# 2_layers.net
KiCad netlist of a schematic drawn in EAGLE
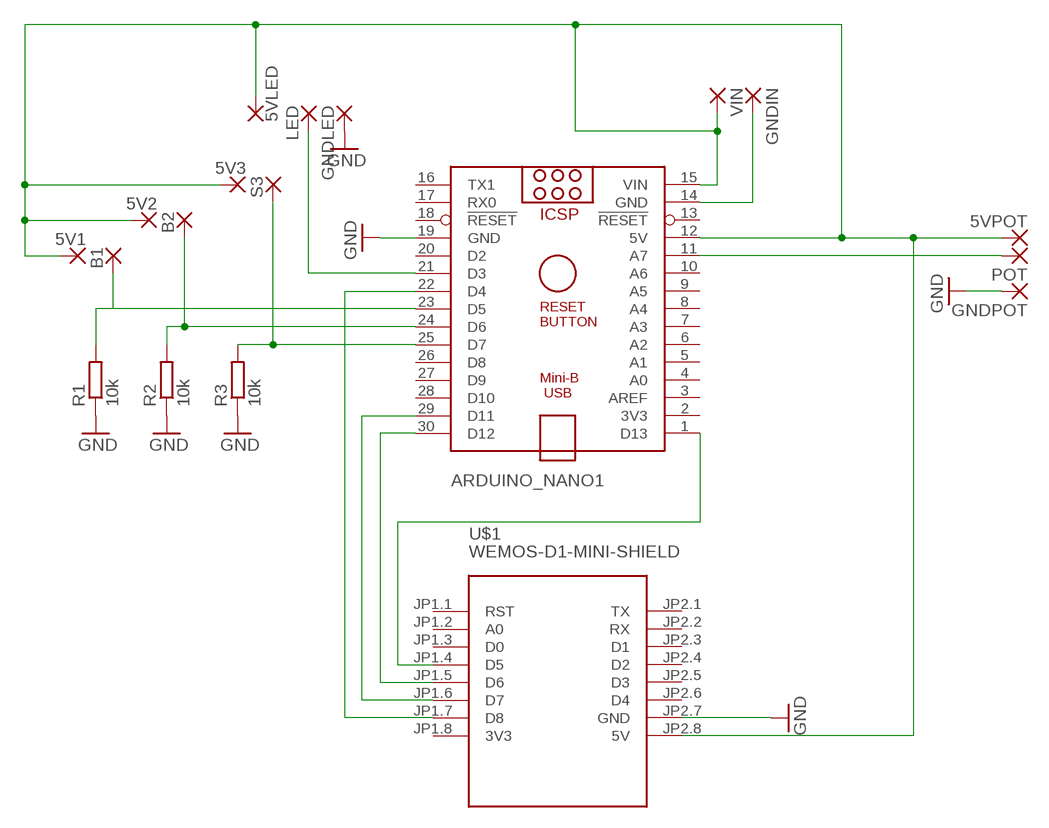
[diagram p0: schematic, sheet 1]

(export (version "E")
  (design (tool "Eeschema 10.0.6"))
  (components
    (comp (ref "5V1")
      (value "1,6/0,8")
      (footprint "eagle-import:1,6_0,8")
      (libsource (lib "eagle-import") (part "1,6/0,8"))
    )
    (comp (ref "5V2")
      (value "1,6/0,8")
      (footprint "eagle-import:1,6_0,8")
      (libsource (lib "eagle-import") (part "1,6/0,8"))
    )
    (comp (ref "5V3")
      (value "1,6/0,8")
      (footprint "eagle-import:1,6_0,8")
      (libsource (lib "eagle-import") (part "1,6/0,8"))
    )
    (comp (ref "5VLED")
      (value "1,6/0,8")
      (footprint "eagle-import:1,6_0,8")
      (libsource (lib "eagle-import") (part "1,6/0,8"))
    )
    (comp (ref "5VPOT")
      (value "1,6/0,8")
      (footprint "eagle-import:1,6_0,8")
      (libsource (lib "eagle-import") (part "1,6/0,8"))
    )
    (comp (ref "ARDUINO_NANO1")
      (value "ARDUINO_NANO")
      (footprint "eagle-import:ARDUINO_NANO")
      (libsource (lib "eagle-import") (part "ARDUINO_NANO"))
    )
    (comp (ref "B1")
      (value "1,6/0,8")
      (footprint "eagle-import:1,6_0,8")
      (libsource (lib "eagle-import") (part "1,6/0,8"))
    )
    (comp (ref "B2")
      (value "1,6/0,8")
      (footprint "eagle-import:1,6_0,8")
      (libsource (lib "eagle-import") (part "1,6/0,8"))
    )
    (comp (ref "GNDIN")
      (value "1,6/0,8")
      (footprint "eagle-import:1,6_0,8")
      (libsource (lib "eagle-import") (part "1,6/0,8"))
    )
    (comp (ref "GNDLED")
      (value "1,6/0,8")
      (footprint "eagle-import:1,6_0,8")
      (libsource (lib "eagle-import") (part "1,6/0,8"))
    )
    (comp (ref "GNDPOT")
      (value "1,6/0,8")
      (footprint "eagle-import:1,6_0,8")
      (libsource (lib "eagle-import") (part "1,6/0,8"))
    )
    (comp (ref "LED")
      (value "1,6/0,8")
      (footprint "eagle-import:1,6_0,8")
      (libsource (lib "eagle-import") (part "1,6/0,8"))
    )
    (comp (ref "POT")
      (value "1,6/0,8")
      (footprint "eagle-import:1,6_0,8")
      (libsource (lib "eagle-import") (part "1,6/0,8"))
    )
    (comp (ref "R1")
      (value "10k")
      (footprint "eagle-import:0207_7")
      (libsource (lib "eagle-import") (part "R-EU_0207/7"))
    )
    (comp (ref "R2")
      (value "10k")
      (footprint "eagle-import:0207_7")
      (libsource (lib "eagle-import") (part "R-EU_0207/7"))
    )
    (comp (ref "R3")
      (value "10k")
      (footprint "eagle-import:0207_7")
      (libsource (lib "eagle-import") (part "R-EU_0207/7"))
    )
    (comp (ref "S3")
      (value "1,6/0,8")
      (footprint "eagle-import:1,6_0,8")
      (libsource (lib "eagle-import") (part "1,6/0,8"))
    )
    (comp (ref "U$1")
      (value "WEMOS-D1-MINI-SHIELD")
      (footprint "eagle-import:WEMOS-D1-MINI-SHIELD")
      (libsource (lib "eagle-import") (part "WEMOS-D1-MINI-SHIELD"))
    )
    (comp (ref "VIN")
      (value "1,6/0,8")
      (footprint "eagle-import:1,6_0,8")
      (libsource (lib "eagle-import") (part "1,6/0,8"))
    )
  )
  (nets
    (net (code "1") (name "/3V3") (class "Default")
      (node (ref "U$1") (pin "JP1.8") (pinfunction "3V3_JP1.8") (pintype "power_in"))
    )
    (net (code "2") (name "GND") (class "Default")
      (node (ref "ARDUINO_NANO1") (pin "19") (pinfunction "GND_19") (pintype "power_in"))
      (node (ref "GNDLED") (pin "1") (pinfunction "P_1") (pintype "passive"))
      (node (ref "GNDPOT") (pin "1") (pinfunction "P_1") (pintype "passive"))
      (node (ref "R1") (pin "1") (pinfunction "1_1") (pintype "passive"))
      (node (ref "R2") (pin "1") (pinfunction "1_1") (pintype "passive"))
      (node (ref "R3") (pin "1") (pinfunction "1_1") (pintype "passive"))
      (node (ref "U$1") (pin "JP2.7") (pinfunction "GND_JP2.7") (pintype "power_in"))
    )
    (net (code "3") (name "Net-(5V1-P)") (class "Default")
      (node (ref "5V1") (pin "1") (pinfunction "P_1") (pintype "passive"))
      (node (ref "5V2") (pin "1") (pinfunction "P_1") (pintype "passive"))
      (node (ref "5V3") (pin "1") (pinfunction "P_1") (pintype "passive"))
      (node (ref "5VLED") (pin "1") (pinfunction "P_1") (pintype "passive"))
      (node (ref "5VPOT") (pin "1") (pinfunction "P_1") (pintype "passive"))
      (node (ref "ARDUINO_NANO1") (pin "12") (pinfunction "5V_12") (pintype "power_in"))
      (node (ref "ARDUINO_NANO1") (pin "15") (pinfunction "VIN_15") (pintype "power_in"))
      (node (ref "U$1") (pin "JP2.8") (pinfunction "5V_JP2.8") (pintype "power_in"))
      (node (ref "VIN") (pin "1") (pinfunction "P_1") (pintype "passive"))
    )
    (net (code "4") (name "Net-(ARDUINO_NANO1-A7)") (class "Default")
      (node (ref "ARDUINO_NANO1") (pin "11") (pinfunction "A7_11") (pintype "bidirectional"))
      (node (ref "POT") (pin "1") (pinfunction "P_1") (pintype "passive"))
    )
    (net (code "5") (name "Net-(ARDUINO_NANO1-D3)") (class "Default")
      (node (ref "ARDUINO_NANO1") (pin "21") (pinfunction "D3_21") (pintype "bidirectional"))
      (node (ref "LED") (pin "1") (pinfunction "P_1") (pintype "passive"))
    )
    (net (code "6") (name "Net-(ARDUINO_NANO1-D4)") (class "Default")
      (node (ref "ARDUINO_NANO1") (pin "22") (pinfunction "D4_22") (pintype "bidirectional"))
      (node (ref "U$1") (pin "JP1.7") (pinfunction "D8_JP1.7") (pintype "bidirectional"))
    )
    (net (code "7") (name "Net-(ARDUINO_NANO1-D5)") (class "Default")
      (node (ref "ARDUINO_NANO1") (pin "23") (pinfunction "D5_23") (pintype "bidirectional"))
      (node (ref "B1") (pin "1") (pinfunction "P_1") (pintype "passive"))
      (node (ref "R1") (pin "2") (pinfunction "2_2") (pintype "passive"))
    )
    (net (code "8") (name "Net-(ARDUINO_NANO1-D6)") (class "Default")
      (node (ref "ARDUINO_NANO1") (pin "24") (pinfunction "D6_24") (pintype "bidirectional"))
      (node (ref "B2") (pin "1") (pinfunction "P_1") (pintype "passive"))
      (node (ref "R2") (pin "2") (pinfunction "2_2") (pintype "passive"))
    )
    (net (code "9") (name "Net-(ARDUINO_NANO1-D7)") (class "Default")
      (node (ref "ARDUINO_NANO1") (pin "25") (pinfunction "D7_25") (pintype "bidirectional"))
      (node (ref "R3") (pin "2") (pinfunction "2_2") (pintype "passive"))
      (node (ref "S3") (pin "1") (pinfunction "P_1") (pintype "passive"))
    )
    (net (code "10") (name "Net-(ARDUINO_NANO1-D11)") (class "Default")
      (node (ref "ARDUINO_NANO1") (pin "29") (pinfunction "D11_29") (pintype "bidirectional"))
      (node (ref "U$1") (pin "JP1.6") (pinfunction "D7_JP1.6") (pintype "bidirectional"))
    )
    (net (code "11") (name "Net-(ARDUINO_NANO1-D12)") (class "Default")
      (node (ref "ARDUINO_NANO1") (pin "30") (pinfunction "D12_30") (pintype "bidirectional"))
      (node (ref "U$1") (pin "JP1.5") (pinfunction "D6_JP1.5") (pintype "bidirectional"))
    )
    (net (code "12") (name "Net-(ARDUINO_NANO1-D13)") (class "Default")
      (node (ref "ARDUINO_NANO1") (pin "1") (pinfunction "D13_1") (pintype "bidirectional"))
      (node (ref "U$1") (pin "JP1.4") (pinfunction "D5_JP1.4") (pintype "bidirectional"))
    )
    (net (code "13") (name "Net-(GNDIN-P)") (class "Default")
      (node (ref "ARDUINO_NANO1") (pin "14") (pinfunction "GND_14") (pintype "power_in"))
      (node (ref "GNDIN") (pin "1") (pinfunction "P_1") (pintype "passive"))
    )
    (net (code "14") (name "unconnected-(ARDUINO_NANO1-3V3-Pad2)") (class "Default")
      (node (ref "ARDUINO_NANO1") (pin "2") (pinfunction "3V3_2") (pintype "output"))
    )
    (net (code "15") (name "unconnected-(ARDUINO_NANO1-A0-Pad4)") (class "Default")
      (node (ref "ARDUINO_NANO1") (pin "4") (pinfunction "A0_4") (pintype "bidirectional"))
    )
    (net (code "16") (name "unconnected-(ARDUINO_NANO1-A1-Pad5)") (class "Default")
      (node (ref "ARDUINO_NANO1") (pin "5") (pinfunction "A1_5") (pintype "bidirectional"))
    )
    (net (code "17") (name "unconnected-(ARDUINO_NANO1-A2-Pad6)") (class "Default")
      (node (ref "ARDUINO_NANO1") (pin "6") (pinfunction "A2_6") (pintype "bidirectional"))
    )
    (net (code "18") (name "unconnected-(ARDUINO_NANO1-A3-Pad7)") (class "Default")
      (node (ref "ARDUINO_NANO1") (pin "7") (pinfunction "A3_7") (pintype "bidirectional"))
    )
    (net (code "19") (name "unconnected-(ARDUINO_NANO1-A4-Pad8)") (class "Default")
      (node (ref "ARDUINO_NANO1") (pin "8") (pinfunction "A4_8") (pintype "bidirectional"))
    )
    (net (code "20") (name "unconnected-(ARDUINO_NANO1-A5-Pad9)") (class "Default")
      (node (ref "ARDUINO_NANO1") (pin "9") (pinfunction "A5_9") (pintype "bidirectional"))
    )
    (net (code "21") (name "unconnected-(ARDUINO_NANO1-A6-Pad10)") (class "Default")
      (node (ref "ARDUINO_NANO1") (pin "10") (pinfunction "A6_10") (pintype "bidirectional"))
    )
    (net (code "22") (name "unconnected-(ARDUINO_NANO1-AREF-Pad3)") (class "Default")
      (node (ref "ARDUINO_NANO1") (pin "3") (pinfunction "AREF_3") (pintype "input"))
    )
    (net (code "23") (name "unconnected-(ARDUINO_NANO1-D2-Pad20)") (class "Default")
      (node (ref "ARDUINO_NANO1") (pin "20") (pinfunction "D2_20") (pintype "bidirectional"))
    )
    (net (code "24") (name "unconnected-(ARDUINO_NANO1-D8-Pad26)") (class "Default")
      (node (ref "ARDUINO_NANO1") (pin "26") (pinfunction "D8_26") (pintype "bidirectional"))
    )
    (net (code "25") (name "unconnected-(ARDUINO_NANO1-D9-Pad27)") (class "Default")
      (node (ref "ARDUINO_NANO1") (pin "27") (pinfunction "D9_27") (pintype "bidirectional"))
    )
    (net (code "26") (name "unconnected-(ARDUINO_NANO1-D10-Pad28)") (class "Default")
      (node (ref "ARDUINO_NANO1") (pin "28") (pinfunction "D10_28") (pintype "bidirectional"))
    )
    (net (code "27") (name "unconnected-(ARDUINO_NANO1-RX0-Pad17)") (class "Default")
      (node (ref "ARDUINO_NANO1") (pin "17") (pinfunction "RX0_17") (pintype "bidirectional"))
    )
    (net (code "28") (name "unconnected-(ARDUINO_NANO1-TX1-Pad16)") (class "Default")
      (node (ref "ARDUINO_NANO1") (pin "16") (pinfunction "TX1_16") (pintype "bidirectional"))
    )
    (net (code "29") (name "unconnected-(ARDUINO_NANO1-~{RESET}-Pad13)") (class "Default")
      (node (ref "ARDUINO_NANO1") (pin "13") (pinfunction "~{RESET}_13") (pintype "input"))
    )
    (net (code "30") (name "unconnected-(ARDUINO_NANO1-~{RESET}-Pad18)") (class "Default")
      (node (ref "ARDUINO_NANO1") (pin "18") (pinfunction "~{RESET}_18") (pintype "input"))
    )
    (net (code "31") (name "unconnected-(U$1-A0-PadJP1.2)") (class "Default")
      (node (ref "U$1") (pin "JP1.2") (pinfunction "A0_JP1.2") (pintype "bidirectional"))
    )
    (net (code "32") (name "unconnected-(U$1-D0-PadJP1.3)") (class "Default")
      (node (ref "U$1") (pin "JP1.3") (pinfunction "D0_JP1.3") (pintype "bidirectional"))
    )
    (net (code "33") (name "unconnected-(U$1-D1-PadJP2.3)") (class "Default")
      (node (ref "U$1") (pin "JP2.3") (pinfunction "D1_JP2.3") (pintype "bidirectional"))
    )
    (net (code "34") (name "unconnected-(U$1-D2-PadJP2.4)") (class "Default")
      (node (ref "U$1") (pin "JP2.4") (pinfunction "D2_JP2.4") (pintype "bidirectional"))
    )
    (net (code "35") (name "unconnected-(U$1-D3-PadJP2.5)") (class "Default")
      (node (ref "U$1") (pin "JP2.5") (pinfunction "D3_JP2.5") (pintype "bidirectional"))
    )
    (net (code "36") (name "unconnected-(U$1-D4-PadJP2.6)") (class "Default")
      (node (ref "U$1") (pin "JP2.6") (pinfunction "D4_JP2.6") (pintype "bidirectional"))
    )
    (net (code "37") (name "unconnected-(U$1-RST-PadJP1.1)") (class "Default")
      (node (ref "U$1") (pin "JP1.1") (pinfunction "RST_JP1.1") (pintype "bidirectional"))
    )
    (net (code "38") (name "unconnected-(U$1-RX-PadJP2.2)") (class "Default")
      (node (ref "U$1") (pin "JP2.2") (pinfunction "RX_JP2.2") (pintype "bidirectional"))
    )
    (net (code "39") (name "unconnected-(U$1-TX-PadJP2.1)") (class "Default")
      (node (ref "U$1") (pin "JP2.1") (pinfunction "TX_JP2.1") (pintype "bidirectional"))
    )
  )
)
